# OECU_BASE6.net
KiCad netlist of a schematic drawn in Altium Designer
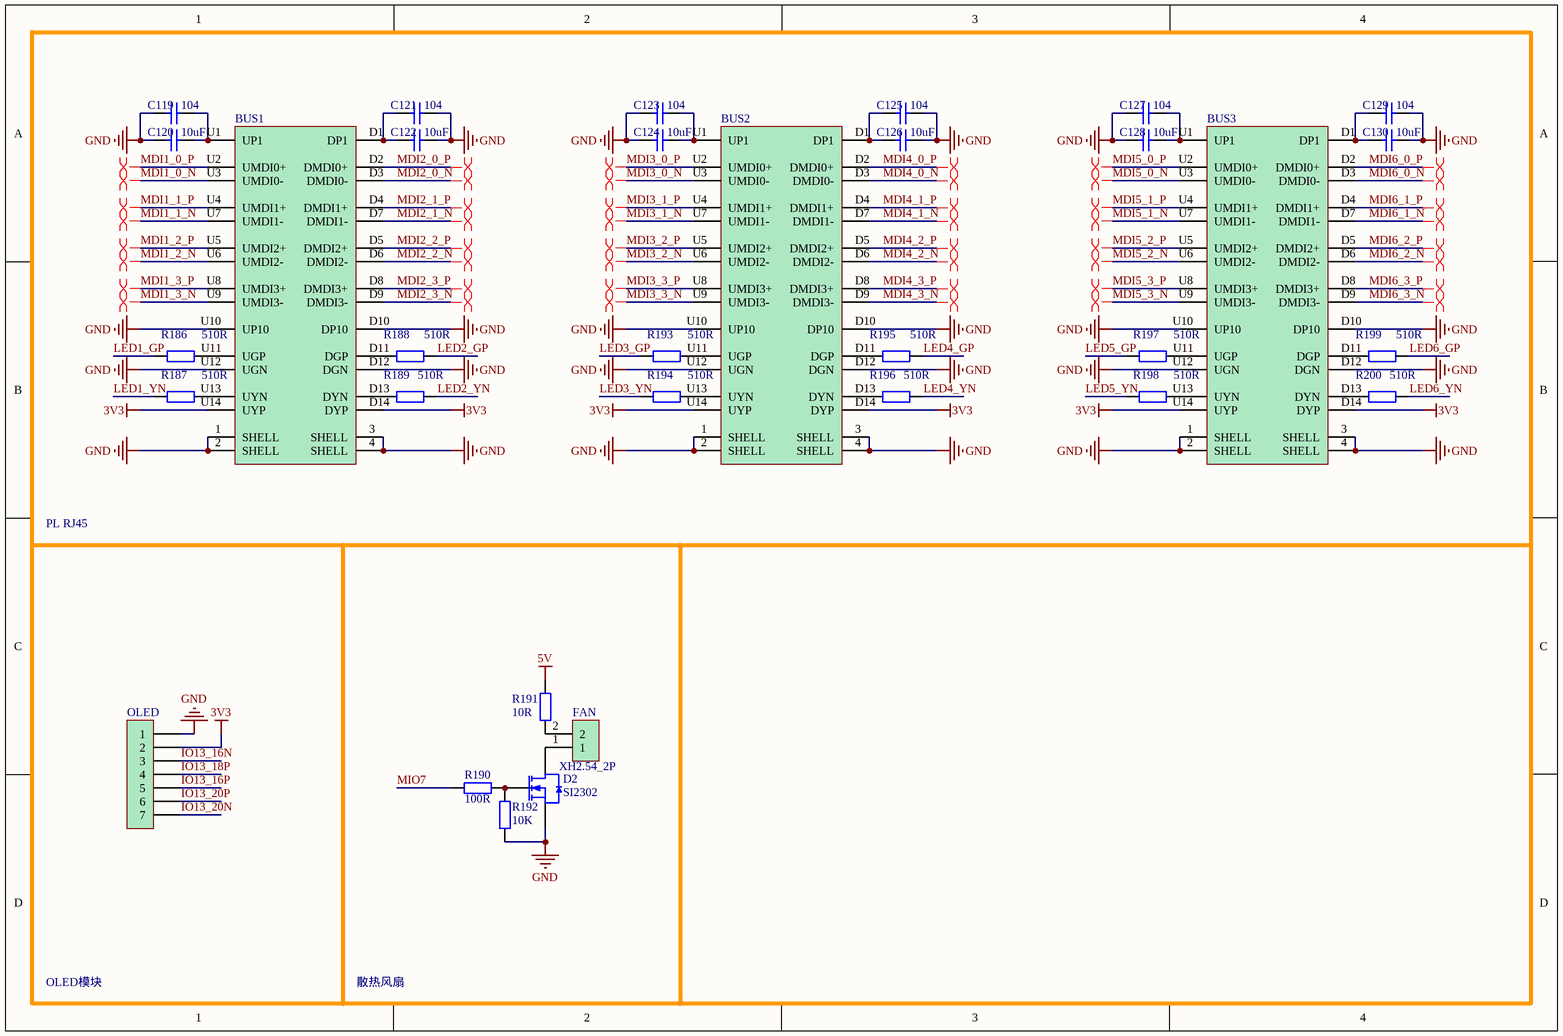
[diagram p0: OECU_BASE6.SchDoc]

(export (version "E")
  (design (tool "Eeschema 10.0.6"))
  (components
    (comp (ref "BUS1")
      (value "RJ45_HR916130H")
      (footprint "HR916130H")
      (libsource (lib "MT_Connector") (part "RJ45_HR916130H"))
    )
    (comp (ref "BUS2")
      (value "RJ45_HR916130H")
      (footprint "HR916130H")
      (libsource (lib "MT_Connector") (part "RJ45_HR916130H"))
    )
    (comp (ref "BUS3")
      (value "RJ45_HR916130H")
      (footprint "HR916130H")
      (libsource (lib "MT_Connector") (part "RJ45_HR916130H"))
    )
    (comp (ref "C119")
      (value "104")
      (footprint "0402")
      (description "贴片电容 0402")
      (libsource (lib "MT_Device") (part "CAP_0402"))
    )
    (comp (ref "C120")
      (value "10uF")
      (footprint "0402")
      (description "贴片电容 0402")
      (libsource (lib "MT_Device") (part "CAP_0402"))
    )
    (comp (ref "C121")
      (value "104")
      (footprint "0402")
      (description "贴片电容 0402")
      (libsource (lib "MT_Device") (part "CAP_0402"))
    )
    (comp (ref "C122")
      (value "10uF")
      (footprint "0402")
      (description "贴片电容 0402")
      (libsource (lib "MT_Device") (part "CAP_0402"))
    )
    (comp (ref "C123")
      (value "104")
      (footprint "0402")
      (description "贴片电容 0402")
      (libsource (lib "MT_Device") (part "CAP_0402"))
    )
    (comp (ref "C124")
      (value "10uF")
      (footprint "0402")
      (description "贴片电容 0402")
      (libsource (lib "MT_Device") (part "CAP_0402"))
    )
    (comp (ref "C125")
      (value "104")
      (footprint "0402")
      (description "贴片电容 0402")
      (libsource (lib "MT_Device") (part "CAP_0402"))
    )
    (comp (ref "C126")
      (value "10uF")
      (footprint "0402")
      (description "贴片电容 0402")
      (libsource (lib "MT_Device") (part "CAP_0402"))
    )
    (comp (ref "C127")
      (value "104")
      (footprint "0402")
      (description "贴片电容 0402")
      (libsource (lib "MT_Device") (part "CAP_0402"))
    )
    (comp (ref "C128")
      (value "10uF")
      (footprint "0402")
      (description "贴片电容 0402")
      (libsource (lib "MT_Device") (part "CAP_0402"))
    )
    (comp (ref "C129")
      (value "104")
      (footprint "0402")
      (description "贴片电容 0402")
      (libsource (lib "MT_Device") (part "CAP_0402"))
    )
    (comp (ref "C130")
      (value "10uF")
      (footprint "0402")
      (description "贴片电容 0402")
      (libsource (lib "MT_Device") (part "CAP_0402"))
    )
    (comp (ref "D2")
      (value "SI2302")
      (footprint "SOT23")
      (description "NMOS")
      (libsource (lib "MT_Device") (part "MOSN_SI2302_SOT23"))
    )
    (comp (ref "FAN")
      (value "XH2.54_2P")
      (footprint "XH2.5_2P")
      (libsource (lib "MT_Connector") (part "XH2.54_2P"))
    )
    (comp (ref "OLED")
      (value "Header_2.54_7P")
      (footprint "HDR1_7P")
      (libsource (lib "MT_Connector") (part "Header_2.54_7P"))
    )
    (comp (ref "R186")
      (value "510R")
      (footprint "R_0402")
      (description "电阻 0402")
      (libsource (lib "MT_Device") (part "RES_0402"))
    )
    (comp (ref "R187")
      (value "510R")
      (footprint "R_0402")
      (description "电阻 0402")
      (libsource (lib "MT_Device") (part "RES_0402"))
    )
    (comp (ref "R188")
      (value "510R")
      (footprint "R_0402")
      (description "电阻 0402")
      (libsource (lib "MT_Device") (part "RES_0402"))
    )
    (comp (ref "R189")
      (value "510R")
      (footprint "R_0402")
      (description "电阻 0402")
      (libsource (lib "") (part "RES_0402_1"))
    )
    (comp (ref "R190")
      (value "100R")
      (footprint "R_0402")
      (description "电阻 0402")
      (libsource (lib "MT_Device") (part "RES_0402"))
    )
    (comp (ref "R191")
      (value "10R")
      (footprint "R_0402")
      (description "电阻 0402")
      (libsource (lib "") (part "RES_0402_2"))
    )
    (comp (ref "R192")
      (value "10K")
      (footprint "R_0402")
      (description "电阻 0402")
      (libsource (lib "") (part "RES_0402_2"))
    )
    (comp (ref "R193")
      (value "510R")
      (footprint "R_0402")
      (description "电阻 0402")
      (libsource (lib "MT_Device") (part "RES_0402"))
    )
    (comp (ref "R194")
      (value "510R")
      (footprint "R_0402")
      (description "电阻 0402")
      (libsource (lib "MT_Device") (part "RES_0402"))
    )
    (comp (ref "R195")
      (value "510R")
      (footprint "R_0402")
      (description "电阻 0402")
      (libsource (lib "MT_Device") (part "RES_0402"))
    )
    (comp (ref "R196")
      (value "510R")
      (footprint "R_0402")
      (description "电阻 0402")
      (libsource (lib "") (part "RES_0402_1"))
    )
    (comp (ref "R197")
      (value "510R")
      (footprint "R_0402")
      (description "电阻 0402")
      (libsource (lib "MT_Device") (part "RES_0402"))
    )
    (comp (ref "R198")
      (value "510R")
      (footprint "R_0402")
      (description "电阻 0402")
      (libsource (lib "MT_Device") (part "RES_0402"))
    )
    (comp (ref "R199")
      (value "510R")
      (footprint "R_0402")
      (description "电阻 0402")
      (libsource (lib "MT_Device") (part "RES_0402"))
    )
    (comp (ref "R200")
      (value "510R")
      (footprint "R_0402")
      (description "电阻 0402")
      (libsource (lib "") (part "RES_0402_1"))
    )
  )
  (nets
    (net (code "1") (name "/IO13_16N") (class "Default")
      (node (ref "OLED") (pin "3") (pinfunction "3_3") (pintype "passive"))
    )
    (net (code "2") (name "/IO13_16P") (class "Default")
      (node (ref "OLED") (pin "5") (pinfunction "5_5") (pintype "passive"))
    )
    (net (code "3") (name "/IO13_18P") (class "Default")
      (node (ref "OLED") (pin "4") (pinfunction "4_4") (pintype "passive"))
    )
    (net (code "4") (name "/IO13_20N") (class "Default")
      (node (ref "OLED") (pin "7") (pinfunction "7_7") (pintype "passive"))
    )
    (net (code "5") (name "/IO13_20P") (class "Default")
      (node (ref "OLED") (pin "6") (pinfunction "6_6") (pintype "passive"))
    )
    (net (code "6") (name "/LED1_GP") (class "Default")
      (node (ref "R186") (pin "1") (pinfunction "1_1") (pintype "passive"))
    )
    (net (code "7") (name "/LED1_YN") (class "Default")
      (node (ref "R187") (pin "1") (pinfunction "1_1") (pintype "passive"))
    )
    (net (code "8") (name "/LED2_GP") (class "Default")
      (node (ref "R188") (pin "2") (pinfunction "2_2") (pintype "passive"))
    )
    (net (code "9") (name "/LED2_YN") (class "Default")
      (node (ref "R189") (pin "1") (pinfunction "1_1") (pintype "passive"))
    )
    (net (code "10") (name "/LED3_GP") (class "Default")
      (node (ref "R193") (pin "1") (pinfunction "1_1") (pintype "passive"))
    )
    (net (code "11") (name "/LED3_YN") (class "Default")
      (node (ref "R194") (pin "1") (pinfunction "1_1") (pintype "passive"))
    )
    (net (code "12") (name "/LED4_GP") (class "Default")
      (node (ref "R195") (pin "2") (pinfunction "2_2") (pintype "passive"))
    )
    (net (code "13") (name "/LED4_YN") (class "Default")
      (node (ref "R196") (pin "1") (pinfunction "1_1") (pintype "passive"))
    )
    (net (code "14") (name "/LED5_GP") (class "Default")
      (node (ref "R197") (pin "1") (pinfunction "1_1") (pintype "passive"))
    )
    (net (code "15") (name "/LED5_YN") (class "Default")
      (node (ref "R198") (pin "1") (pinfunction "1_1") (pintype "passive"))
    )
    (net (code "16") (name "/LED6_GP") (class "Default")
      (node (ref "R199") (pin "2") (pinfunction "2_2") (pintype "passive"))
    )
    (net (code "17") (name "/LED6_YN") (class "Default")
      (node (ref "R200") (pin "1") (pinfunction "1_1") (pintype "passive"))
    )
    (net (code "18") (name "/MDI1_0_N") (class "Default")
      (node (ref "BUS1") (pin "U3") (pinfunction "UMDI0-_U3") (pintype "passive"))
    )
    (net (code "19") (name "/MDI1_0_P") (class "Default")
      (node (ref "BUS1") (pin "U2") (pinfunction "UMDI0+_U2") (pintype "passive"))
    )
    (net (code "20") (name "/MDI1_1_N") (class "Default")
      (node (ref "BUS1") (pin "U7") (pinfunction "UMDI1-_U7") (pintype "passive"))
    )
    (net (code "21") (name "/MDI1_1_P") (class "Default")
      (node (ref "BUS1") (pin "U4") (pinfunction "UMDI1+_U4") (pintype "passive"))
    )
    (net (code "22") (name "/MDI1_2_N") (class "Default")
      (node (ref "BUS1") (pin "U6") (pinfunction "UMDI2-_U6") (pintype "passive"))
    )
    (net (code "23") (name "/MDI1_2_P") (class "Default")
      (node (ref "BUS1") (pin "U5") (pinfunction "UMDI2+_U5") (pintype "passive"))
    )
    (net (code "24") (name "/MDI1_3_N") (class "Default")
      (node (ref "BUS1") (pin "U9") (pinfunction "UMDI3-_U9") (pintype "passive"))
    )
    (net (code "25") (name "/MDI1_3_P") (class "Default")
      (node (ref "BUS1") (pin "U8") (pinfunction "UMDI3+_U8") (pintype "passive"))
    )
    (net (code "26") (name "/MDI2_0_N") (class "Default")
      (node (ref "BUS1") (pin "D3") (pinfunction "DMDI0-_D3") (pintype "passive"))
    )
    (net (code "27") (name "/MDI2_0_P") (class "Default")
      (node (ref "BUS1") (pin "D2") (pinfunction "DMDI0+_D2") (pintype "passive"))
    )
    (net (code "28") (name "/MDI2_1_N") (class "Default")
      (node (ref "BUS1") (pin "D7") (pinfunction "DMDI1-_D7") (pintype "passive"))
    )
    (net (code "29") (name "/MDI2_1_P") (class "Default")
      (node (ref "BUS1") (pin "D4") (pinfunction "DMDI1+_D4") (pintype "passive"))
    )
    (net (code "30") (name "/MDI2_2_N") (class "Default")
      (node (ref "BUS1") (pin "D6") (pinfunction "DMDI2-_D6") (pintype "passive"))
    )
    (net (code "31") (name "/MDI2_2_P") (class "Default")
      (node (ref "BUS1") (pin "D5") (pinfunction "DMDI2+_D5") (pintype "passive"))
    )
    (net (code "32") (name "/MDI2_3_N") (class "Default")
      (node (ref "BUS1") (pin "D9") (pinfunction "DMDI3-_D9") (pintype "passive"))
    )
    (net (code "33") (name "/MDI2_3_P") (class "Default")
      (node (ref "BUS1") (pin "D8") (pinfunction "DMDI3+_D8") (pintype "passive"))
    )
    (net (code "34") (name "/MDI3_0_N") (class "Default")
      (node (ref "BUS2") (pin "U3") (pinfunction "UMDI0-_U3") (pintype "passive"))
    )
    (net (code "35") (name "/MDI3_0_P") (class "Default")
      (node (ref "BUS2") (pin "U2") (pinfunction "UMDI0+_U2") (pintype "passive"))
    )
    (net (code "36") (name "/MDI3_1_N") (class "Default")
      (node (ref "BUS2") (pin "U7") (pinfunction "UMDI1-_U7") (pintype "passive"))
    )
    (net (code "37") (name "/MDI3_1_P") (class "Default")
      (node (ref "BUS2") (pin "U4") (pinfunction "UMDI1+_U4") (pintype "passive"))
    )
    (net (code "38") (name "/MDI3_2_N") (class "Default")
      (node (ref "BUS2") (pin "U6") (pinfunction "UMDI2-_U6") (pintype "passive"))
    )
    (net (code "39") (name "/MDI3_2_P") (class "Default")
      (node (ref "BUS2") (pin "U5") (pinfunction "UMDI2+_U5") (pintype "passive"))
    )
    (net (code "40") (name "/MDI3_3_N") (class "Default")
      (node (ref "BUS2") (pin "U9") (pinfunction "UMDI3-_U9") (pintype "passive"))
    )
    (net (code "41") (name "/MDI3_3_P") (class "Default")
      (node (ref "BUS2") (pin "U8") (pinfunction "UMDI3+_U8") (pintype "passive"))
    )
    (net (code "42") (name "/MDI4_0_N") (class "Default")
      (node (ref "BUS2") (pin "D3") (pinfunction "DMDI0-_D3") (pintype "passive"))
    )
    (net (code "43") (name "/MDI4_0_P") (class "Default")
      (node (ref "BUS2") (pin "D2") (pinfunction "DMDI0+_D2") (pintype "passive"))
    )
    (net (code "44") (name "/MDI4_1_N") (class "Default")
      (node (ref "BUS2") (pin "D7") (pinfunction "DMDI1-_D7") (pintype "passive"))
    )
    (net (code "45") (name "/MDI4_1_P") (class "Default")
      (node (ref "BUS2") (pin "D4") (pinfunction "DMDI1+_D4") (pintype "passive"))
    )
    (net (code "46") (name "/MDI4_2_N") (class "Default")
      (node (ref "BUS2") (pin "D6") (pinfunction "DMDI2-_D6") (pintype "passive"))
    )
    (net (code "47") (name "/MDI4_2_P") (class "Default")
      (node (ref "BUS2") (pin "D5") (pinfunction "DMDI2+_D5") (pintype "passive"))
    )
    (net (code "48") (name "/MDI4_3_N") (class "Default")
      (node (ref "BUS2") (pin "D9") (pinfunction "DMDI3-_D9") (pintype "passive"))
    )
    (net (code "49") (name "/MDI4_3_P") (class "Default")
      (node (ref "BUS2") (pin "D8") (pinfunction "DMDI3+_D8") (pintype "passive"))
    )
    (net (code "50") (name "/MDI5_0_N") (class "Default")
      (node (ref "BUS3") (pin "U3") (pinfunction "UMDI0-_U3") (pintype "passive"))
    )
    (net (code "51") (name "/MDI5_0_P") (class "Default")
      (node (ref "BUS3") (pin "U2") (pinfunction "UMDI0+_U2") (pintype "passive"))
    )
    (net (code "52") (name "/MDI5_1_N") (class "Default")
      (node (ref "BUS3") (pin "U7") (pinfunction "UMDI1-_U7") (pintype "passive"))
    )
    (net (code "53") (name "/MDI5_1_P") (class "Default")
      (node (ref "BUS3") (pin "U4") (pinfunction "UMDI1+_U4") (pintype "passive"))
    )
    (net (code "54") (name "/MDI5_2_N") (class "Default")
      (node (ref "BUS3") (pin "U6") (pinfunction "UMDI2-_U6") (pintype "passive"))
    )
    (net (code "55") (name "/MDI5_2_P") (class "Default")
      (node (ref "BUS3") (pin "U5") (pinfunction "UMDI2+_U5") (pintype "passive"))
    )
    (net (code "56") (name "/MDI5_3_N") (class "Default")
      (node (ref "BUS3") (pin "U9") (pinfunction "UMDI3-_U9") (pintype "passive"))
    )
    (net (code "57") (name "/MDI5_3_P") (class "Default")
      (node (ref "BUS3") (pin "U8") (pinfunction "UMDI3+_U8") (pintype "passive"))
    )
    (net (code "58") (name "/MDI6_0_N") (class "Default")
      (node (ref "BUS3") (pin "D3") (pinfunction "DMDI0-_D3") (pintype "passive"))
    )
    (net (code "59") (name "/MDI6_0_P") (class "Default")
      (node (ref "BUS3") (pin "D2") (pinfunction "DMDI0+_D2") (pintype "passive"))
    )
    (net (code "60") (name "/MDI6_1_N") (class "Default")
      (node (ref "BUS3") (pin "D7") (pinfunction "DMDI1-_D7") (pintype "passive"))
    )
    (net (code "61") (name "/MDI6_1_P") (class "Default")
      (node (ref "BUS3") (pin "D4") (pinfunction "DMDI1+_D4") (pintype "passive"))
    )
    (net (code "62") (name "/MDI6_2_N") (class "Default")
      (node (ref "BUS3") (pin "D6") (pinfunction "DMDI2-_D6") (pintype "passive"))
    )
    (net (code "63") (name "/MDI6_2_P") (class "Default")
      (node (ref "BUS3") (pin "D5") (pinfunction "DMDI2+_D5") (pintype "passive"))
    )
    (net (code "64") (name "/MDI6_3_N") (class "Default")
      (node (ref "BUS3") (pin "D9") (pinfunction "DMDI3-_D9") (pintype "passive"))
    )
    (net (code "65") (name "/MDI6_3_P") (class "Default")
      (node (ref "BUS3") (pin "D8") (pinfunction "DMDI3+_D8") (pintype "passive"))
    )
    (net (code "66") (name "/MIO7") (class "Default")
      (node (ref "R190") (pin "1") (pinfunction "1_1") (pintype "passive"))
    )
    (net (code "67") (name "3V3") (class "Default")
      (node (ref "BUS1") (pin "D14") (pinfunction "DYP_D14") (pintype "passive"))
      (node (ref "BUS1") (pin "U14") (pinfunction "UYP_U14") (pintype "passive"))
      (node (ref "BUS2") (pin "D14") (pinfunction "DYP_D14") (pintype "passive"))
      (node (ref "BUS2") (pin "U14") (pinfunction "UYP_U14") (pintype "passive"))
      (node (ref "BUS3") (pin "D14") (pinfunction "DYP_D14") (pintype "passive"))
      (node (ref "BUS3") (pin "U14") (pinfunction "UYP_U14") (pintype "passive"))
      (node (ref "OLED") (pin "2") (pinfunction "2_2") (pintype "passive"))
    )
    (net (code "68") (name "5V") (class "Default")
      (node (ref "R191") (pin "1") (pinfunction "1_1") (pintype "passive"))
    )
    (net (code "69") (name "GND") (class "Default")
      (node (ref "BUS1") (pin "1") (pinfunction "SHELL_1") (pintype "passive"))
      (node (ref "BUS1") (pin "2") (pinfunction "SHELL_2") (pintype "passive"))
      (node (ref "BUS1") (pin "3") (pinfunction "SHELL_3") (pintype "passive"))
      (node (ref "BUS1") (pin "4") (pinfunction "SHELL_4") (pintype "passive"))
      (node (ref "BUS1") (pin "D10") (pinfunction "DP10_D10") (pintype "passive"))
      (node (ref "BUS1") (pin "D12") (pinfunction "DGN_D12") (pintype "passive"))
      (node (ref "BUS1") (pin "U10") (pinfunction "UP10_U10") (pintype "passive"))
      (node (ref "BUS1") (pin "U12") (pinfunction "UGN_U12") (pintype "passive"))
      (node (ref "BUS2") (pin "1") (pinfunction "SHELL_1") (pintype "passive"))
      (node (ref "BUS2") (pin "2") (pinfunction "SHELL_2") (pintype "passive"))
      (node (ref "BUS2") (pin "3") (pinfunction "SHELL_3") (pintype "passive"))
      (node (ref "BUS2") (pin "4") (pinfunction "SHELL_4") (pintype "passive"))
      (node (ref "BUS2") (pin "D10") (pinfunction "DP10_D10") (pintype "passive"))
      (node (ref "BUS2") (pin "D12") (pinfunction "DGN_D12") (pintype "passive"))
      (node (ref "BUS2") (pin "U10") (pinfunction "UP10_U10") (pintype "passive"))
      (node (ref "BUS2") (pin "U12") (pinfunction "UGN_U12") (pintype "passive"))
      (node (ref "BUS3") (pin "1") (pinfunction "SHELL_1") (pintype "passive"))
      (node (ref "BUS3") (pin "2") (pinfunction "SHELL_2") (pintype "passive"))
      (node (ref "BUS3") (pin "3") (pinfunction "SHELL_3") (pintype "passive"))
      (node (ref "BUS3") (pin "4") (pinfunction "SHELL_4") (pintype "passive"))
      (node (ref "BUS3") (pin "D10") (pinfunction "DP10_D10") (pintype "passive"))
      (node (ref "BUS3") (pin "D12") (pinfunction "DGN_D12") (pintype "passive"))
      (node (ref "BUS3") (pin "U10") (pinfunction "UP10_U10") (pintype "passive"))
      (node (ref "BUS3") (pin "U12") (pinfunction "UGN_U12") (pintype "passive"))
      (node (ref "C119") (pin "1") (pinfunction "1_1") (pintype "passive"))
      (node (ref "C120") (pin "1") (pinfunction "1_1") (pintype "passive"))
      (node (ref "C121") (pin "1") (pinfunction "1_1") (pintype "passive"))
      (node (ref "C122") (pin "1") (pinfunction "1_1") (pintype "passive"))
      (node (ref "C123") (pin "1") (pinfunction "1_1") (pintype "passive"))
      (node (ref "C124") (pin "1") (pinfunction "1_1") (pintype "passive"))
      (node (ref "C125") (pin "1") (pinfunction "1_1") (pintype "passive"))
      (node (ref "C126") (pin "1") (pinfunction "1_1") (pintype "passive"))
      (node (ref "C127") (pin "1") (pinfunction "1_1") (pintype "passive"))
      (node (ref "C128") (pin "1") (pinfunction "1_1") (pintype "passive"))
      (node (ref "C129") (pin "1") (pinfunction "1_1") (pintype "passive"))
      (node (ref "C130") (pin "1") (pinfunction "1_1") (pintype "passive"))
      (node (ref "D2") (pin "2") (pinfunction "S_2") (pintype "passive"))
      (node (ref "OLED") (pin "1") (pinfunction "1_1") (pintype "passive"))
      (node (ref "R192") (pin "2") (pinfunction "2_2") (pintype "passive"))
    )
    (net (code "70") (name "Net-(BUS1-DGP)") (class "Default")
      (node (ref "BUS1") (pin "D11") (pinfunction "DGP_D11") (pintype "passive"))
      (node (ref "R188") (pin "1") (pinfunction "1_1") (pintype "passive"))
    )
    (net (code "71") (name "Net-(BUS1-DP1)") (class "Default")
      (node (ref "BUS1") (pin "D1") (pinfunction "DP1_D1") (pintype "passive"))
      (node (ref "C121") (pin "2") (pinfunction "2_2") (pintype "passive"))
      (node (ref "C122") (pin "2") (pinfunction "2_2") (pintype "passive"))
    )
    (net (code "72") (name "Net-(BUS1-DYN)") (class "Default")
      (node (ref "BUS1") (pin "D13") (pinfunction "DYN_D13") (pintype "passive"))
      (node (ref "R189") (pin "2") (pinfunction "2_2") (pintype "passive"))
    )
    (net (code "73") (name "Net-(BUS1-UGP)") (class "Default")
      (node (ref "BUS1") (pin "U11") (pinfunction "UGP_U11") (pintype "passive"))
      (node (ref "R186") (pin "2") (pinfunction "2_2") (pintype "passive"))
    )
    (net (code "74") (name "Net-(BUS1-UP1)") (class "Default")
      (node (ref "BUS1") (pin "U1") (pinfunction "UP1_U1") (pintype "passive"))
      (node (ref "C119") (pin "2") (pinfunction "2_2") (pintype "passive"))
      (node (ref "C120") (pin "2") (pinfunction "2_2") (pintype "passive"))
    )
    (net (code "75") (name "Net-(BUS1-UYN)") (class "Default")
      (node (ref "BUS1") (pin "U13") (pinfunction "UYN_U13") (pintype "passive"))
      (node (ref "R187") (pin "2") (pinfunction "2_2") (pintype "passive"))
    )
    (net (code "76") (name "Net-(BUS2-DGP)") (class "Default")
      (node (ref "BUS2") (pin "D11") (pinfunction "DGP_D11") (pintype "passive"))
      (node (ref "R195") (pin "1") (pinfunction "1_1") (pintype "passive"))
    )
    (net (code "77") (name "Net-(BUS2-DP1)") (class "Default")
      (node (ref "BUS2") (pin "D1") (pinfunction "DP1_D1") (pintype "passive"))
      (node (ref "C125") (pin "2") (pinfunction "2_2") (pintype "passive"))
      (node (ref "C126") (pin "2") (pinfunction "2_2") (pintype "passive"))
    )
    (net (code "78") (name "Net-(BUS2-DYN)") (class "Default")
      (node (ref "BUS2") (pin "D13") (pinfunction "DYN_D13") (pintype "passive"))
      (node (ref "R196") (pin "2") (pinfunction "2_2") (pintype "passive"))
    )
    (net (code "79") (name "Net-(BUS2-UGP)") (class "Default")
      (node (ref "BUS2") (pin "U11") (pinfunction "UGP_U11") (pintype "passive"))
      (node (ref "R193") (pin "2") (pinfunction "2_2") (pintype "passive"))
    )
    (net (code "80") (name "Net-(BUS2-UP1)") (class "Default")
      (node (ref "BUS2") (pin "U1") (pinfunction "UP1_U1") (pintype "passive"))
      (node (ref "C123") (pin "2") (pinfunction "2_2") (pintype "passive"))
      (node (ref "C124") (pin "2") (pinfunction "2_2") (pintype "passive"))
    )
    (net (code "81") (name "Net-(BUS2-UYN)") (class "Default")
      (node (ref "BUS2") (pin "U13") (pinfunction "UYN_U13") (pintype "passive"))
      (node (ref "R194") (pin "2") (pinfunction "2_2") (pintype "passive"))
    )
    (net (code "82") (name "Net-(BUS3-DGP)") (class "Default")
      (node (ref "BUS3") (pin "D11") (pinfunction "DGP_D11") (pintype "passive"))
      (node (ref "R199") (pin "1") (pinfunction "1_1") (pintype "passive"))
    )
    (net (code "83") (name "Net-(BUS3-DP1)") (class "Default")
      (node (ref "BUS3") (pin "D1") (pinfunction "DP1_D1") (pintype "passive"))
      (node (ref "C129") (pin "2") (pinfunction "2_2") (pintype "passive"))
      (node (ref "C130") (pin "2") (pinfunction "2_2") (pintype "passive"))
    )
    (net (code "84") (name "Net-(BUS3-DYN)") (class "Default")
      (node (ref "BUS3") (pin "D13") (pinfunction "DYN_D13") (pintype "passive"))
      (node (ref "R200") (pin "2") (pinfunction "2_2") (pintype "passive"))
    )
    (net (code "85") (name "Net-(BUS3-UGP)") (class "Default")
      (node (ref "BUS3") (pin "U11") (pinfunction "UGP_U11") (pintype "passive"))
      (node (ref "R197") (pin "2") (pinfunction "2_2") (pintype "passive"))
    )
    (net (code "86") (name "Net-(BUS3-UP1)") (class "Default")
      (node (ref "BUS3") (pin "U1") (pinfunction "UP1_U1") (pintype "passive"))
      (node (ref "C127") (pin "2") (pinfunction "2_2") (pintype "passive"))
      (node (ref "C128") (pin "2") (pinfunction "2_2") (pintype "passive"))
    )
    (net (code "87") (name "Net-(BUS3-UYN)") (class "Default")
      (node (ref "BUS3") (pin "U13") (pinfunction "UYN_U13") (pintype "passive"))
      (node (ref "R198") (pin "2") (pinfunction "2_2") (pintype "passive"))
    )
    (net (code "88") (name "Net-(D2-D)") (class "Default")
      (node (ref "D2") (pin "3") (pinfunction "D_3") (pintype "passive"))
      (node (ref "FAN") (pin "1") (pinfunction "1_1") (pintype "passive"))
    )
    (net (code "89") (name "Net-(D2-G)") (class "Default")
      (node (ref "D2") (pin "1") (pinfunction "G_1") (pintype "passive"))
      (node (ref "R190") (pin "2") (pinfunction "2_2") (pintype "passive"))
      (node (ref "R192") (pin "1") (pinfunction "1_1") (pintype "passive"))
    )
    (net (code "90") (name "Net-(FAN-Pad2)") (class "Default")
      (node (ref "FAN") (pin "2") (pinfunction "2_2") (pintype "passive"))
      (node (ref "R191") (pin "2") (pinfunction "2_2") (pintype "passive"))
    )
  )
)
